# 23-TEST_AUTOMATION.net
KiCad netlist of a schematic drawn in Altium Designer
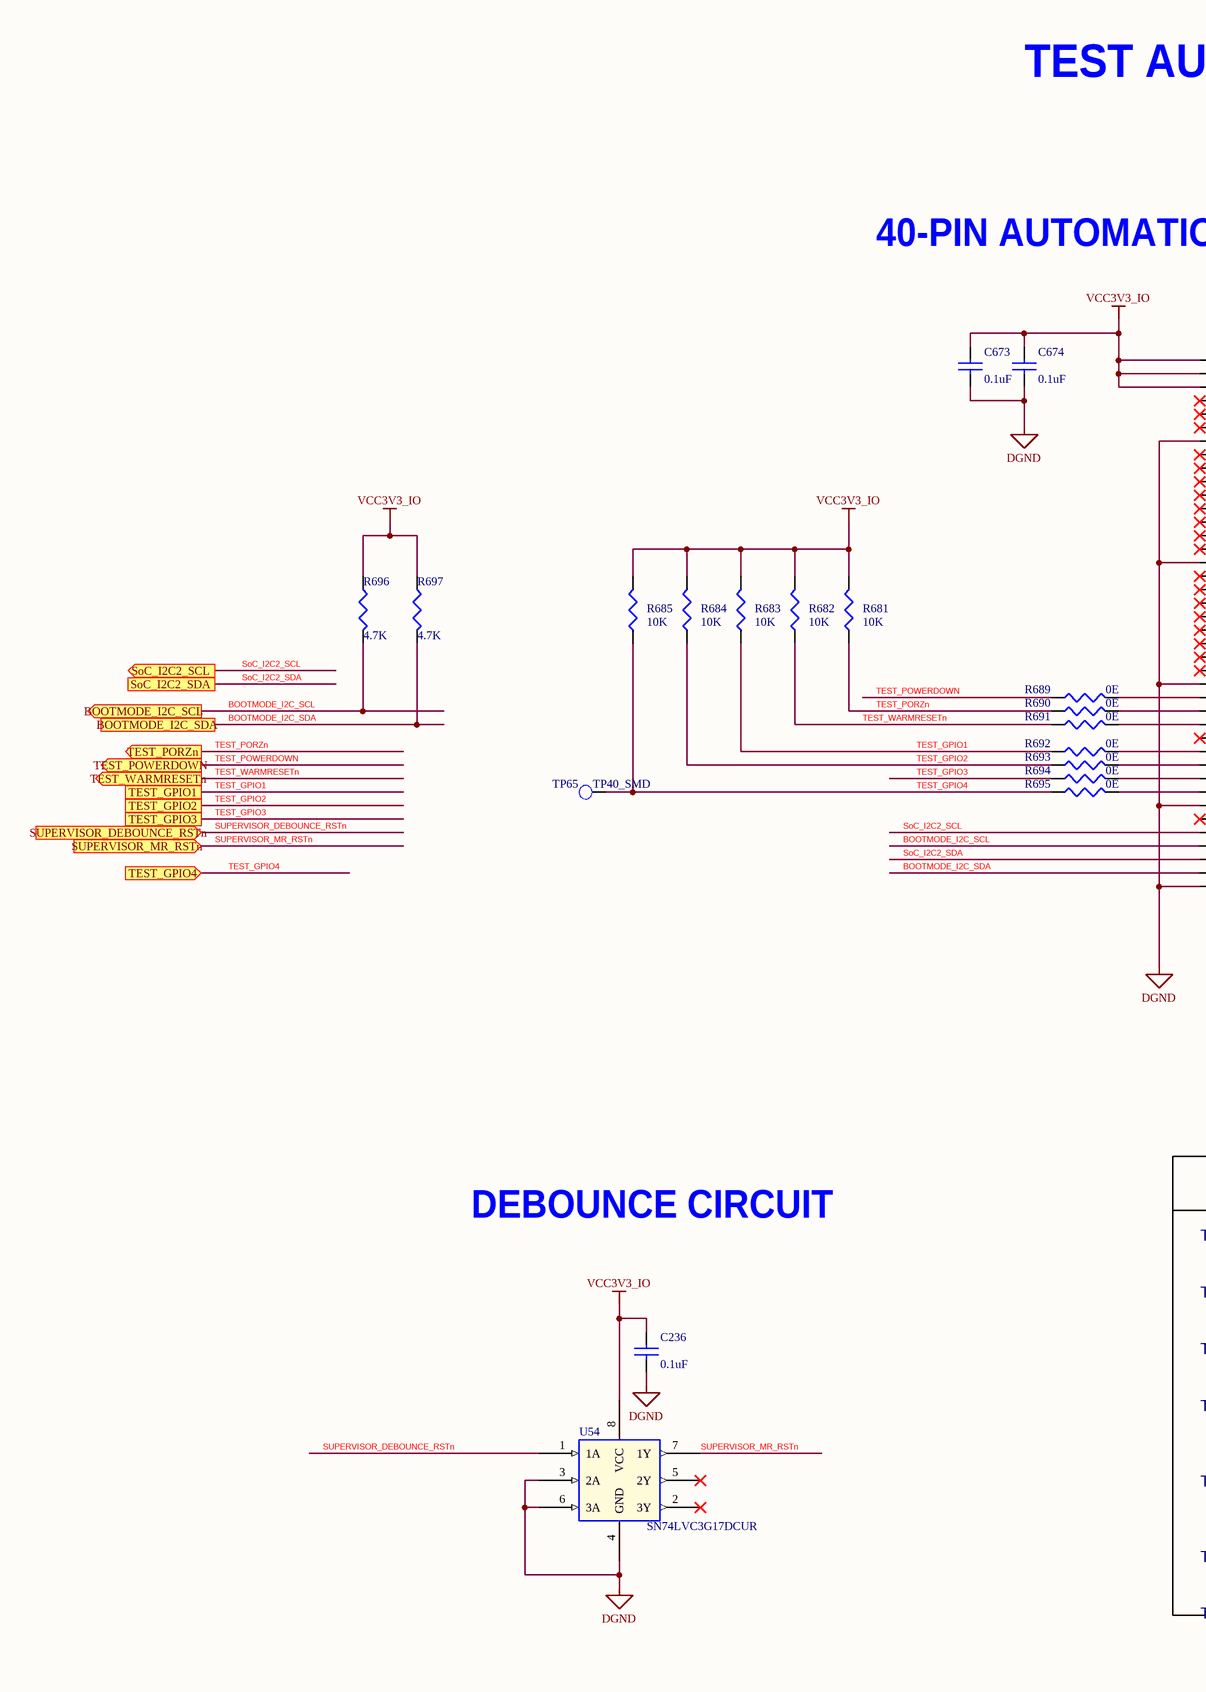
[diagram p0: 23-TEST AUTOMATION.SchDoc, left]
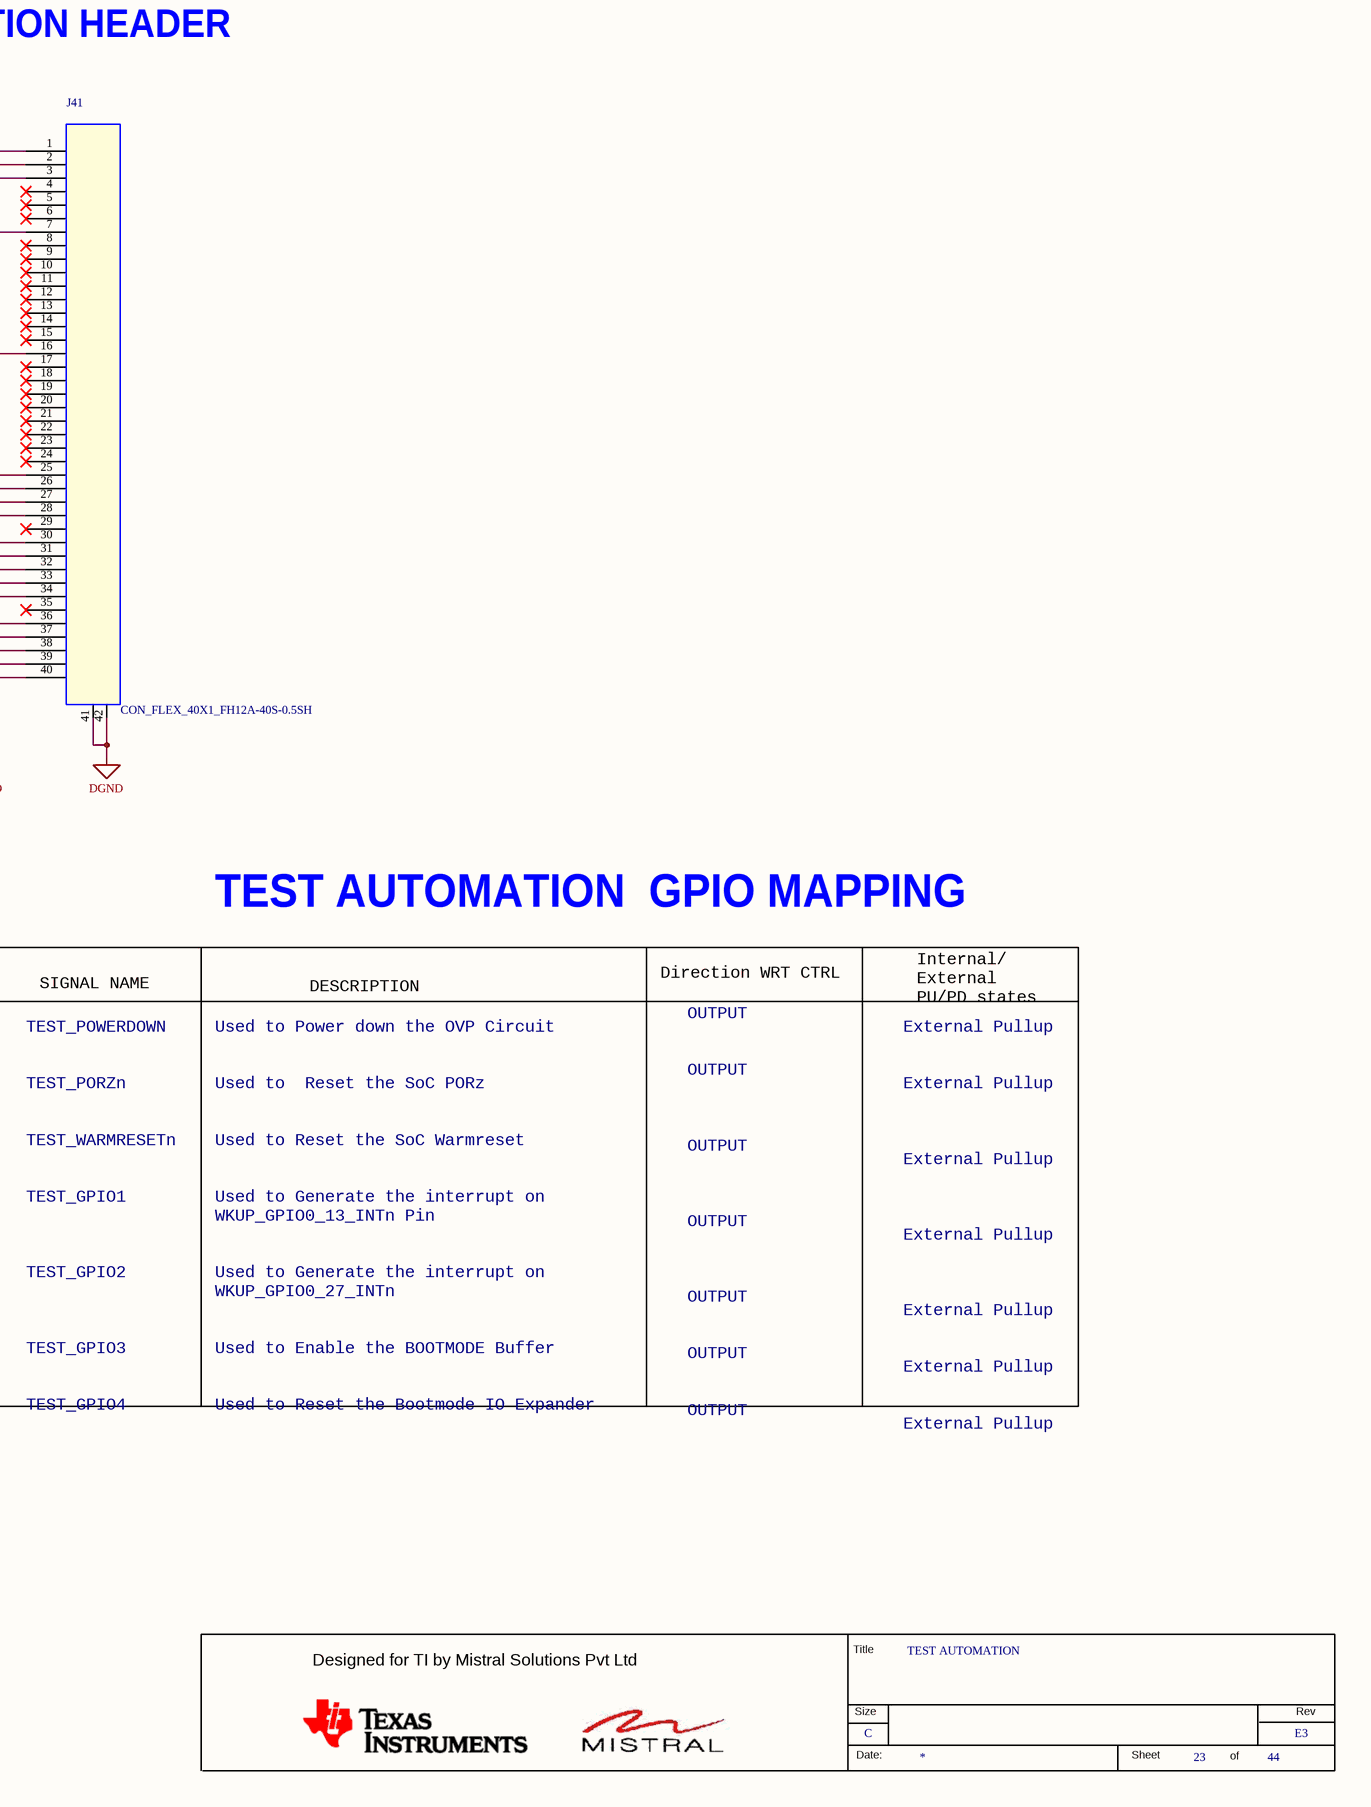
[diagram p1: 23-TEST AUTOMATION.SchDoc, right]

(export (version "E")
  (design (tool "Eeschema 10.0.6"))
  (components
    (comp (ref "C236")
      (value "0.1uF")
      (footprint "CAP0201_0-5")
      (description "CAP CERAMIC 0.1uF 16V 10% X5R 0201")
      (fields
        (field (name "MISTRAL PART NO") "120009030072-R")
        (field (name "MFR_PART_NUMBER") "GRM033R61C104KE84J")
      )
      (libsource (lib "*") (part "CAP_Dup5"))
    )
    (comp (ref "C673")
      (value "0.1uF")
      (footprint "CAP0201_0-5")
      (description "CAP CERAMIC 0.1uF 16V 10% X5R 0201")
      (fields (field (name "DISTRIBUTOR_PART_NUMBER") "490-16742-1-ND") (field (name "VOLTAGE") "16V"))
      (libsource (lib "*") (part "CAP_Dup5"))
    )
    (comp (ref "C674")
      (value "0.1uF")
      (footprint "CAP0201_0-5")
      (description "CAP CERAMIC 0.1uF 16V 10% X5R 0201")
      (fields
        (field (name "MISTRAL PART NO") "120009030072-R")
        (field (name "MFR_PART_NUMBER") "GRM033R61C104KE84J")
      )
      (libsource (lib "*") (part "CAP_Dup5"))
    )
    (comp (ref "J41")
      (value "CON_FLEX_40X1_FH12A-40S-0.5SH")
      (footprint "CON_FLEX40X1_FH12A_S_R_S")
      (description "CON FPC 40X1 0.50MM PITCH RT TOP SMD")
      (fields
        (field (name "DISTRIBUTOR_PART_NUMBER") "HFK40CT-ND")
        (field (name "MFR_PART_NUMBER") "FH12A-40S-0.5SH(55)")
      )
      (libsource (lib "*") (part "CON_FLEX_40X1_FH12A-40S-0.5SH"))
    )
    (comp (ref "R681")
      (value "10K")
      (footprint "RES0402_0-5")
      (description "RES 10K 1/16W 5% 0402")
      (fields
        (field (name "MISTRAL PART NO") "110009030208-R")
        (field (name "MFR_PART_NUMBER") "RC0402JR-0710KL")
      )
      (libsource (lib "*") (part "RESISTOR_Dup5"))
    )
    (comp (ref "R682")
      (value "10K")
      (footprint "RES0402_0-5")
      (description "RES 10K 1/16W 5% 0402")
      (fields
        (field (name "MISTRAL PART NO") "110009030208-R")
        (field (name "MFR_PART_NUMBER") "RC0402JR-0710KL")
      )
      (libsource (lib "*") (part "RESISTOR_Dup5"))
    )
    (comp (ref "R683")
      (value "10K")
      (footprint "RES0402_0-5")
      (description "RES 10K 1/16W 5% 0402")
      (fields
        (field (name "MISTRAL PART NO") "110009030208-R")
        (field (name "MFR_PART_NUMBER") "RC0402JR-0710KL")
      )
      (libsource (lib "*") (part "RESISTOR_Dup5"))
    )
    (comp (ref "R684")
      (value "10K")
      (footprint "RES0402_0-5")
      (description "RES 10K 1/16W 5% 0402")
      (fields
        (field (name "MISTRAL PART NO") "110009030208-R")
        (field (name "MFR_PART_NUMBER") "RC0402JR-0710KL")
      )
      (libsource (lib "*") (part "RESISTOR_Dup5"))
    )
    (comp (ref "R685")
      (value "10K")
      (footprint "RES0402_0-5")
      (description "RES 10K 1/16W 5% 0402")
      (fields
        (field (name "MISTRAL PART NO") "110009030208-R")
        (field (name "MFR_PART_NUMBER") "RC0402JR-0710KL")
      )
      (libsource (lib "*") (part "RESISTOR_Dup5"))
    )
    (comp (ref "R689")
      (value "0E")
      (footprint "RES0402_0-5")
      (description "RES 0E 1/16W 0402")
      (fields (field (name "DISTRIBUTOR_PART_NUMBER") "541-0.0JCT-ND") (field (name "VOLTAGE") "NA"))
      (libsource (lib "*") (part "RESISTOR_Dup4"))
    )
    (comp (ref "R690")
      (value "0E")
      (footprint "RES0402_0-5")
      (description "RES 0E 1/16W 0402")
      (fields
        (field (name "MISTRAL PART NO") "110010080019-P")
        (field (name "MFR_PART_NUMBER") "CRCW04020000Z0ED")
      )
      (libsource (lib "*") (part "RESISTOR_Dup4"))
    )
    (comp (ref "R691")
      (value "0E")
      (footprint "RES0402_0-5")
      (description "RES 0E 1/16W 0402")
      (fields (field (name "DISTRIBUTOR_PART_NUMBER") "541-0.0JCT-ND") (field (name "VOLTAGE") "NA"))
      (libsource (lib "*") (part "RESISTOR_Dup4"))
    )
    (comp (ref "R692")
      (value "0E")
      (footprint "RES0402_0-5")
      (description "RES 0E 1/16W 0402")
      (fields (field (name "DISTRIBUTOR_PART_NUMBER") "541-0.0JCT-ND") (field (name "VOLTAGE") "NA"))
      (libsource (lib "*") (part "RESISTOR_Dup4"))
    )
    (comp (ref "R693")
      (value "0E")
      (footprint "RES0402_0-5")
      (description "RES 0E 1/16W 0402")
      (fields (field (name "DISTRIBUTOR_PART_NUMBER") "541-0.0JCT-ND") (field (name "VOLTAGE") "NA"))
      (libsource (lib "*") (part "RESISTOR_Dup4"))
    )
    (comp (ref "R694")
      (value "0E")
      (footprint "RES0402_0-5")
      (description "RES 0E 1/16W 0402")
      (fields
        (field (name "MISTRAL PART NO") "110010080019-P")
        (field (name "MFR_PART_NUMBER") "CRCW04020000Z0ED")
      )
      (libsource (lib "*") (part "RESISTOR_Dup4"))
    )
    (comp (ref "R695")
      (value "0E")
      (footprint "RES0402_0-5")
      (description "RES 0E 1/16W 0402")
      (fields (field (name "DISTRIBUTOR_PART_NUMBER") "541-0.0JCT-ND") (field (name "VOLTAGE") "NA"))
      (libsource (lib "*") (part "RESISTOR_Dup4"))
    )
    (comp (ref "R696")
      (value "4.7K")
      (footprint "RES0402")
      (description "RES 4.7K 1/16W 5% 0402")
      (fields (field (name "DISTRIBUTOR_PART_NUMBER") "311-4.7KJRCT-ND") (field (name "VOLTAGE") "NA"))
      (libsource (lib "*") (part "RESISTOR_Dup5"))
    )
    (comp (ref "R697")
      (value "4.7K")
      (footprint "RES0402")
      (description "RES 4.7K 1/16W 5% 0402")
      (fields (field (name "DISTRIBUTOR_PART_NUMBER") "311-4.7KJRCT-ND") (field (name "VOLTAGE") "NA"))
      (libsource (lib "*") (part "RESISTOR_Dup5"))
    )
    (comp (ref "TP65")
      (value "TP40_SMD")
      (footprint "TP40_SMD")
      (description "TESTPOINT CIR 40 SMD")
      (fields (field (name "MISTRAL PART NO") "130009030933") (field (name "DISTRIBUTOR_PART_NUMBER") "NA"))
      (libsource (lib "*") (part "TESTPOINT"))
    )
    (comp (ref "U54")
      (value "SN74LVC3G17DCUR")
      (footprint "VSSOP8_19-68_85X95_0-9")
      (description "IC TRIPLE SCHMITT-TRIGGER BUFFER VSSOP8")
      (fields (field (name "DISTRIBUTOR_PART_NUMBER") "296-18818-1-ND") (field (name "VOLTAGE") "NA"))
      (libsource (lib "*") (part "SN74LVC3G17DCUR_VSSOP8"))
    )
  )
  (nets
    (net (code "1") (name "/BOOTMODE_I2C_SCL") (class "Default")
      (node (ref "J41") (pin "37") (pinfunction "37_37") (pintype "passive"))
      (node (ref "R696") (pin "2") (pinfunction "2_2") (pintype "passive"))
    )
    (net (code "2") (name "/BOOTMODE_I2C_SDA") (class "Default")
      (node (ref "J41") (pin "39") (pinfunction "39_39") (pintype "passive"))
      (node (ref "R697") (pin "2") (pinfunction "2_2") (pintype "passive"))
    )
    (net (code "3") (name "/SUPERVISOR_DEBOUNCE_RSTn") (class "Default")
      (node (ref "U54") (pin "1") (pinfunction "1A_1") (pintype "input"))
    )
    (net (code "4") (name "/SUPERVISOR_MR_RSTn") (class "Default")
      (node (ref "U54") (pin "7") (pinfunction "1Y_7") (pintype "output"))
    )
    (net (code "5") (name "/SoC_I2C2_SCL") (class "Default")
      (node (ref "J41") (pin "36") (pinfunction "36_36") (pintype "passive"))
    )
    (net (code "6") (name "/SoC_I2C2_SDA") (class "Default")
      (node (ref "J41") (pin "38") (pinfunction "38_38") (pintype "passive"))
    )
    (net (code "7") (name "/TEST_GPIO1") (class "Default")
      (node (ref "R683") (pin "1") (pinfunction "1_1") (pintype "passive"))
      (node (ref "R692") (pin "1") (pinfunction "1_1") (pintype "passive"))
    )
    (net (code "8") (name "/TEST_GPIO2") (class "Default")
      (node (ref "R684") (pin "1") (pinfunction "1_1") (pintype "passive"))
      (node (ref "R693") (pin "1") (pinfunction "1_1") (pintype "passive"))
    )
    (net (code "9") (name "/TEST_GPIO3") (class "Default")
      (node (ref "R694") (pin "1") (pinfunction "1_1") (pintype "passive"))
    )
    (net (code "10") (name "/TEST_GPIO4") (class "Default")
      (node (ref "R685") (pin "1") (pinfunction "1_1") (pintype "passive"))
      (node (ref "R695") (pin "1") (pinfunction "1_1") (pintype "passive"))
      (node (ref "TP65") (pin "1") (pinfunction "TP_1") (pintype "passive"))
    )
    (net (code "11") (name "/TEST_PORZn") (class "Default")
      (node (ref "R681") (pin "1") (pinfunction "1_1") (pintype "passive"))
      (node (ref "R690") (pin "1") (pinfunction "1_1") (pintype "passive"))
    )
    (net (code "12") (name "/TEST_POWERDOWN") (class "Default")
      (node (ref "R689") (pin "1") (pinfunction "1_1") (pintype "passive"))
    )
    (net (code "13") (name "/TEST_WARMRESETn") (class "Default")
      (node (ref "R682") (pin "1") (pinfunction "1_1") (pintype "passive"))
      (node (ref "R691") (pin "1") (pinfunction "1_1") (pintype "passive"))
    )
    (net (code "14") (name "DGND") (class "Default")
      (node (ref "C236") (pin "2") (pinfunction "2_2") (pintype "passive"))
      (node (ref "C673") (pin "2") (pinfunction "2_2") (pintype "passive"))
      (node (ref "C674") (pin "2") (pinfunction "2_2") (pintype "passive"))
      (node (ref "J41") (pin "16") (pinfunction "16_16") (pintype "passive"))
      (node (ref "J41") (pin "25") (pinfunction "25_25") (pintype "passive"))
      (node (ref "J41") (pin "34") (pinfunction "34_34") (pintype "passive"))
      (node (ref "J41") (pin "40") (pinfunction "40_40") (pintype "passive"))
      (node (ref "J41") (pin "41") (pinfunction "41_41") (pintype "passive"))
      (node (ref "J41") (pin "42") (pinfunction "42_42") (pintype "passive"))
      (node (ref "J41") (pin "7") (pinfunction "7_7") (pintype "passive"))
      (node (ref "U54") (pin "3") (pinfunction "2A_3") (pintype "input"))
      (node (ref "U54") (pin "4") (pinfunction "GND_4") (pintype "power_in"))
      (node (ref "U54") (pin "6") (pinfunction "3A_6") (pintype "input"))
    )
    (net (code "15") (name "Net-(J41-Pad26)") (class "Default")
      (node (ref "J41") (pin "26") (pinfunction "26_26") (pintype "passive"))
      (node (ref "R689") (pin "2") (pinfunction "2_2") (pintype "passive"))
    )
    (net (code "16") (name "Net-(J41-Pad27)") (class "Default")
      (node (ref "J41") (pin "27") (pinfunction "27_27") (pintype "passive"))
      (node (ref "R690") (pin "2") (pinfunction "2_2") (pintype "passive"))
    )
    (net (code "17") (name "Net-(J41-Pad28)") (class "Default")
      (node (ref "J41") (pin "28") (pinfunction "28_28") (pintype "passive"))
      (node (ref "R691") (pin "2") (pinfunction "2_2") (pintype "passive"))
    )
    (net (code "18") (name "Net-(J41-Pad30)") (class "Default")
      (node (ref "J41") (pin "30") (pinfunction "30_30") (pintype "passive"))
      (node (ref "R692") (pin "2") (pinfunction "2_2") (pintype "passive"))
    )
    (net (code "19") (name "Net-(J41-Pad31)") (class "Default")
      (node (ref "J41") (pin "31") (pinfunction "31_31") (pintype "passive"))
      (node (ref "R693") (pin "2") (pinfunction "2_2") (pintype "passive"))
    )
    (net (code "20") (name "Net-(J41-Pad32)") (class "Default")
      (node (ref "J41") (pin "32") (pinfunction "32_32") (pintype "passive"))
      (node (ref "R694") (pin "2") (pinfunction "2_2") (pintype "passive"))
    )
    (net (code "21") (name "Net-(J41-Pad33)") (class "Default")
      (node (ref "J41") (pin "33") (pinfunction "33_33") (pintype "passive"))
      (node (ref "R695") (pin "2") (pinfunction "2_2") (pintype "passive"))
    )
    (net (code "22") (name "VCC3V3_IO") (class "Default")
      (node (ref "C236") (pin "1") (pinfunction "1_1") (pintype "passive"))
      (node (ref "C673") (pin "1") (pinfunction "1_1") (pintype "passive"))
      (node (ref "C674") (pin "1") (pinfunction "1_1") (pintype "passive"))
      (node (ref "J41") (pin "1") (pinfunction "1_1") (pintype "passive"))
      (node (ref "J41") (pin "2") (pinfunction "2_2") (pintype "passive"))
      (node (ref "J41") (pin "3") (pinfunction "3_3") (pintype "passive"))
      (node (ref "R681") (pin "2") (pinfunction "2_2") (pintype "passive"))
      (node (ref "R682") (pin "2") (pinfunction "2_2") (pintype "passive"))
      (node (ref "R683") (pin "2") (pinfunction "2_2") (pintype "passive"))
      (node (ref "R684") (pin "2") (pinfunction "2_2") (pintype "passive"))
      (node (ref "R685") (pin "2") (pinfunction "2_2") (pintype "passive"))
      (node (ref "R696") (pin "1") (pinfunction "1_1") (pintype "passive"))
      (node (ref "R697") (pin "1") (pinfunction "1_1") (pintype "passive"))
      (node (ref "U54") (pin "8") (pinfunction "VCC_8") (pintype "power_in"))
    )
    (net (code "23") (name "unconnected-(J41-Pad4)") (class "Default")
      (node (ref "J41") (pin "4") (pinfunction "4_4") (pintype "passive+no_connect"))
    )
    (net (code "24") (name "unconnected-(J41-Pad5)") (class "Default")
      (node (ref "J41") (pin "5") (pinfunction "5_5") (pintype "passive+no_connect"))
    )
    (net (code "25") (name "unconnected-(J41-Pad6)") (class "Default")
      (node (ref "J41") (pin "6") (pinfunction "6_6") (pintype "passive+no_connect"))
    )
    (net (code "26") (name "unconnected-(J41-Pad8)") (class "Default")
      (node (ref "J41") (pin "8") (pinfunction "8_8") (pintype "passive+no_connect"))
    )
    (net (code "27") (name "unconnected-(J41-Pad9)") (class "Default")
      (node (ref "J41") (pin "9") (pinfunction "9_9") (pintype "passive+no_connect"))
    )
    (net (code "28") (name "unconnected-(J41-Pad10)") (class "Default")
      (node (ref "J41") (pin "10") (pinfunction "10_10") (pintype "passive+no_connect"))
    )
    (net (code "29") (name "unconnected-(J41-Pad11)") (class "Default")
      (node (ref "J41") (pin "11") (pinfunction "11_11") (pintype "passive+no_connect"))
    )
    (net (code "30") (name "unconnected-(J41-Pad12)") (class "Default")
      (node (ref "J41") (pin "12") (pinfunction "12_12") (pintype "passive+no_connect"))
    )
    (net (code "31") (name "unconnected-(J41-Pad13)") (class "Default")
      (node (ref "J41") (pin "13") (pinfunction "13_13") (pintype "passive+no_connect"))
    )
    (net (code "32") (name "unconnected-(J41-Pad14)") (class "Default")
      (node (ref "J41") (pin "14") (pinfunction "14_14") (pintype "passive+no_connect"))
    )
    (net (code "33") (name "unconnected-(J41-Pad15)") (class "Default")
      (node (ref "J41") (pin "15") (pinfunction "15_15") (pintype "passive+no_connect"))
    )
    (net (code "34") (name "unconnected-(J41-Pad17)") (class "Default")
      (node (ref "J41") (pin "17") (pinfunction "17_17") (pintype "passive+no_connect"))
    )
    (net (code "35") (name "unconnected-(J41-Pad18)") (class "Default")
      (node (ref "J41") (pin "18") (pinfunction "18_18") (pintype "passive+no_connect"))
    )
    (net (code "36") (name "unconnected-(J41-Pad19)") (class "Default")
      (node (ref "J41") (pin "19") (pinfunction "19_19") (pintype "passive+no_connect"))
    )
    (net (code "37") (name "unconnected-(J41-Pad20)") (class "Default")
      (node (ref "J41") (pin "20") (pinfunction "20_20") (pintype "passive+no_connect"))
    )
    (net (code "38") (name "unconnected-(J41-Pad21)") (class "Default")
      (node (ref "J41") (pin "21") (pinfunction "21_21") (pintype "passive+no_connect"))
    )
    (net (code "39") (name "unconnected-(J41-Pad22)") (class "Default")
      (node (ref "J41") (pin "22") (pinfunction "22_22") (pintype "passive+no_connect"))
    )
    (net (code "40") (name "unconnected-(J41-Pad23)") (class "Default")
      (node (ref "J41") (pin "23") (pinfunction "23_23") (pintype "passive+no_connect"))
    )
    (net (code "41") (name "unconnected-(J41-Pad24)") (class "Default")
      (node (ref "J41") (pin "24") (pinfunction "24_24") (pintype "passive+no_connect"))
    )
    (net (code "42") (name "unconnected-(J41-Pad29)") (class "Default")
      (node (ref "J41") (pin "29") (pinfunction "29_29") (pintype "passive+no_connect"))
    )
    (net (code "43") (name "unconnected-(J41-Pad35)") (class "Default")
      (node (ref "J41") (pin "35") (pinfunction "35_35") (pintype "passive+no_connect"))
    )
    (net (code "44") (name "unconnected-(U54-2Y-Pad5)") (class "Default")
      (node (ref "U54") (pin "5") (pinfunction "2Y_5") (pintype "output+no_connect"))
    )
    (net (code "45") (name "unconnected-(U54-3Y-Pad2)") (class "Default")
      (node (ref "U54") (pin "2") (pinfunction "3Y_2") (pintype "output+no_connect"))
    )
  )
)
